# i21_JOYBIT_v03__4_4x.net
KiCad netlist of a schematic drawn in EAGLE
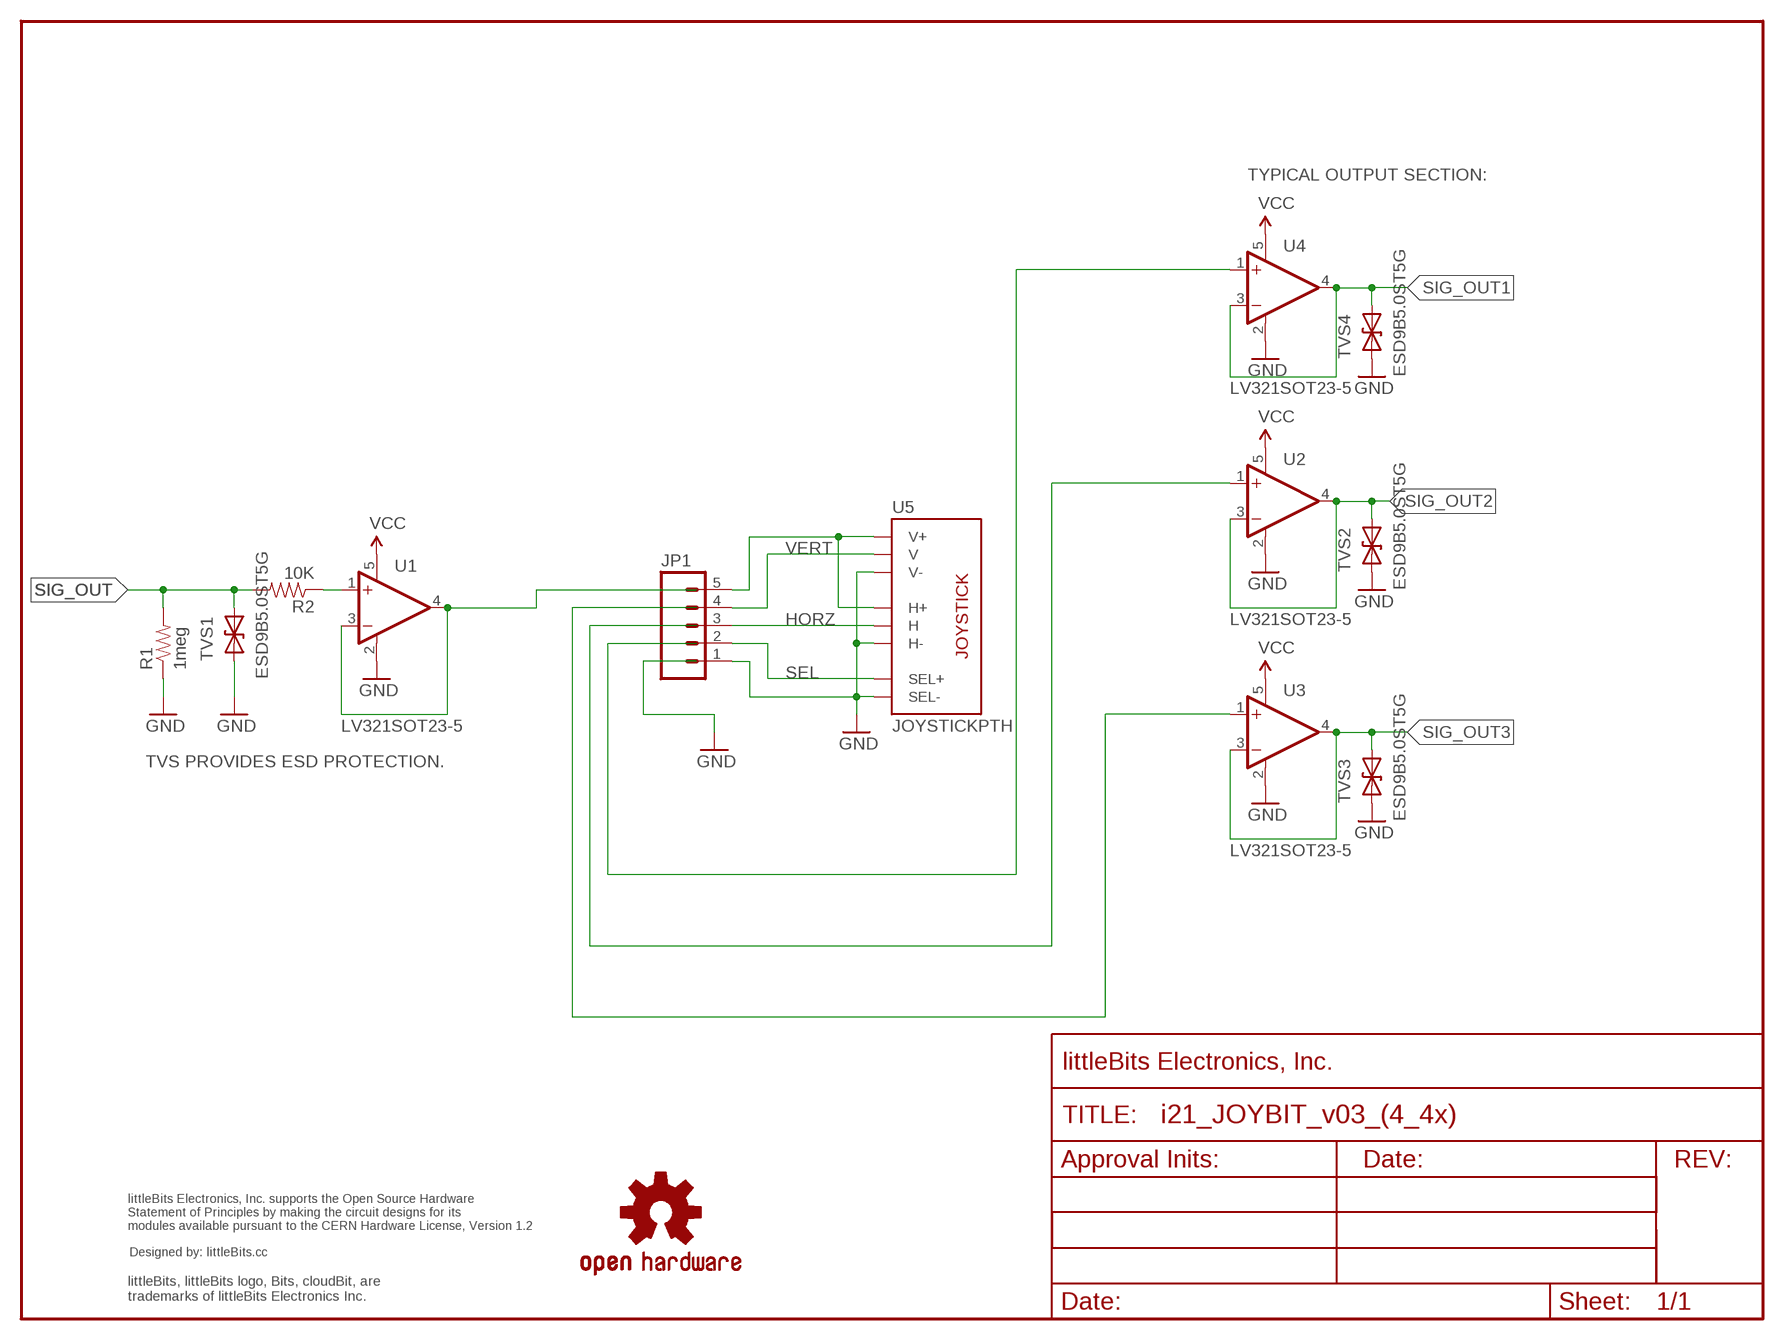
[diagram p0: schematic, sheet 1]

(export (version "E")
  (design (tool "Eeschema 10.0.6"))
  (components
    (comp (ref "FRAME1")
      (value "FRAME-LETTER")
      (footprint "eagle-import:FABDWG01-OHW")
      (libsource (lib "eagle-import") (part "FRAME-LETTER"))
    )
    (comp (ref "JP1")
      (value "M05PTH")
      (footprint "eagle-import:1X05")
      (libsource (lib "eagle-import") (part "M05PTH"))
    )
    (comp (ref "R1")
      (value "1meg")
      (footprint "eagle-import:RES-0603")
      (libsource (lib "eagle-import") (part "RESISTOR0603"))
    )
    (comp (ref "R2")
      (value "10K")
      (footprint "eagle-import:RES-0603")
      (libsource (lib "eagle-import") (part "RESISTOR0603"))
    )
    (comp (ref "TVS1")
      (value "ESD9B5.0ST5G")
      (footprint "eagle-import:SOD-923")
      (libsource (lib "eagle-import") (part "DIODE-TVSSOD-923"))
    )
    (comp (ref "TVS2")
      (value "ESD9B5.0ST5G")
      (footprint "eagle-import:SOD-923")
      (libsource (lib "eagle-import") (part "DIODE-TVSSOD-923"))
    )
    (comp (ref "TVS3")
      (value "ESD9B5.0ST5G")
      (footprint "eagle-import:SOD-923")
      (libsource (lib "eagle-import") (part "DIODE-TVSSOD-923"))
    )
    (comp (ref "TVS4")
      (value "ESD9B5.0ST5G")
      (footprint "eagle-import:SOD-923")
      (libsource (lib "eagle-import") (part "DIODE-TVSSOD-923"))
    )
    (comp (ref "U$2")
      (value "OSHWCREDIT")
      (footprint "eagle-import:OSHWCREDIT")
      (libsource (lib "eagle-import") (part "OSHWCREDIT"))
    )
    (comp (ref "U$3")
      (value "OSHW-LOGOL")
      (footprint "eagle-import:OSHW-LOGO-L")
      (libsource (lib "eagle-import") (part "OSHW-LOGOL"))
    )
    (comp (ref "U1")
      (value "LV321SOT23-5")
      (footprint "eagle-import:SOT23-5")
      (libsource (lib "eagle-import") (part "LV321SOT23-5"))
    )
    (comp (ref "U2")
      (value "LV321SOT23-5")
      (footprint "eagle-import:SOT23-5")
      (libsource (lib "eagle-import") (part "LV321SOT23-5"))
    )
    (comp (ref "U3")
      (value "LV321SOT23-5")
      (footprint "eagle-import:SOT23-5")
      (libsource (lib "eagle-import") (part "LV321SOT23-5"))
    )
    (comp (ref "U4")
      (value "LV321SOT23-5")
      (footprint "eagle-import:SOT23-5")
      (libsource (lib "eagle-import") (part "LV321SOT23-5"))
    )
    (comp (ref "U5")
      (value "JOYSTICKPTH")
      (footprint "eagle-import:JOYSTICK")
      (libsource (lib "eagle-import") (part "JOYSTICKPTH"))
    )
  )
  (nets
    (net (code "1") (name "/HORZ") (class "Default")
      (node (ref "JP1") (pin "3") (pinfunction "3_3") (pintype "passive"))
      (node (ref "U5") (pin "H2") (pinfunction "H_H2") (pintype "bidirectional"))
    )
    (net (code "2") (name "/SEL") (class "Default")
      (node (ref "JP1") (pin "2") (pinfunction "2_2") (pintype "passive"))
      (node (ref "U5") (pin "B1A") (pinfunction "SEL+_B1A") (pintype "bidirectional"))
    )
    (net (code "3") (name "/VERT") (class "Default")
      (node (ref "JP1") (pin "4") (pinfunction "4_4") (pintype "passive"))
      (node (ref "U5") (pin "V2") (pinfunction "V_V2") (pintype "bidirectional"))
    )
    (net (code "4") (name "GND") (class "Default")
      (node (ref "JP1") (pin "1") (pinfunction "1_1") (pintype "passive"))
      (node (ref "R1") (pin "1") (pinfunction "1_1") (pintype "passive"))
      (node (ref "TVS1") (pin "1") (pinfunction "A_1") (pintype "passive"))
      (node (ref "TVS2") (pin "1") (pinfunction "A_1") (pintype "passive"))
      (node (ref "TVS3") (pin "1") (pinfunction "A_1") (pintype "passive"))
      (node (ref "TVS4") (pin "1") (pinfunction "A_1") (pintype "passive"))
      (node (ref "U1") (pin "2") (pinfunction "V-_2") (pintype "power_in"))
      (node (ref "U2") (pin "2") (pinfunction "V-_2") (pintype "power_in"))
      (node (ref "U3") (pin "2") (pinfunction "V-_2") (pintype "power_in"))
      (node (ref "U4") (pin "2") (pinfunction "V-_2") (pintype "power_in"))
      (node (ref "U5") (pin "B2A") (pinfunction "SEL-_B2A") (pintype "bidirectional"))
      (node (ref "U5") (pin "H3") (pinfunction "H-_H3") (pintype "bidirectional"))
      (node (ref "U5") (pin "V3") (pinfunction "V-_V3") (pintype "bidirectional"))
    )
    (net (code "5") (name "Net-(U1-+IN)") (class "Default")
      (node (ref "R2") (pin "1") (pinfunction "1_1") (pintype "passive"))
      (node (ref "U1") (pin "1") (pinfunction "+IN_1") (pintype "input"))
    )
    (net (code "6") (name "Net-(U1--IN)") (class "Default")
      (node (ref "U1") (pin "3") (pinfunction "-IN_3") (pintype "input"))
      (node (ref "U1") (pin "4") (pinfunction "OUT_4") (pintype "output"))
    )
    (net (code "7") (name "Net-(U5-H+)") (class "Default")
      (node (ref "JP1") (pin "5") (pinfunction "5_5") (pintype "passive"))
      (node (ref "U5") (pin "H1") (pinfunction "H+_H1") (pintype "bidirectional"))
      (node (ref "U5") (pin "V1") (pinfunction "V+_V1") (pintype "bidirectional"))
    )
    (net (code "8") (name "SIG_OUT") (class "Default")
      (node (ref "R1") (pin "2") (pinfunction "2_2") (pintype "passive"))
      (node (ref "R2") (pin "2") (pinfunction "2_2") (pintype "passive"))
      (node (ref "TVS1") (pin "2") (pinfunction "C_2") (pintype "passive"))
    )
    (net (code "9") (name "SIG_OUT1") (class "Default")
      (node (ref "TVS4") (pin "2") (pinfunction "C_2") (pintype "passive"))
      (node (ref "U4") (pin "3") (pinfunction "-IN_3") (pintype "input"))
      (node (ref "U4") (pin "4") (pinfunction "OUT_4") (pintype "output"))
    )
    (net (code "10") (name "SIG_OUT2") (class "Default")
      (node (ref "TVS2") (pin "2") (pinfunction "C_2") (pintype "passive"))
      (node (ref "U2") (pin "3") (pinfunction "-IN_3") (pintype "input"))
      (node (ref "U2") (pin "4") (pinfunction "OUT_4") (pintype "output"))
    )
    (net (code "11") (name "SIG_OUT3") (class "Default")
      (node (ref "TVS3") (pin "2") (pinfunction "C_2") (pintype "passive"))
      (node (ref "U3") (pin "3") (pinfunction "-IN_3") (pintype "input"))
      (node (ref "U3") (pin "4") (pinfunction "OUT_4") (pintype "output"))
    )
    (net (code "12") (name "VCC") (class "Default")
      (node (ref "U1") (pin "5") (pinfunction "V+_5") (pintype "power_in"))
      (node (ref "U2") (pin "5") (pinfunction "V+_5") (pintype "power_in"))
      (node (ref "U3") (pin "5") (pinfunction "V+_5") (pintype "power_in"))
      (node (ref "U4") (pin "5") (pinfunction "V+_5") (pintype "power_in"))
    )
    (net (code "13") (name "unconnected-(U2-+IN-Pad1)") (class "Default")
      (node (ref "U2") (pin "1") (pinfunction "+IN_1") (pintype "input"))
    )
    (net (code "14") (name "unconnected-(U3-+IN-Pad1)") (class "Default")
      (node (ref "U3") (pin "1") (pinfunction "+IN_1") (pintype "input"))
    )
    (net (code "15") (name "unconnected-(U4-+IN-Pad1)") (class "Default")
      (node (ref "U4") (pin "1") (pinfunction "+IN_1") (pintype "input"))
    )
  )
)
